# RelaySchematic.net
KiCad netlist of a schematic drawn in Altium Designer
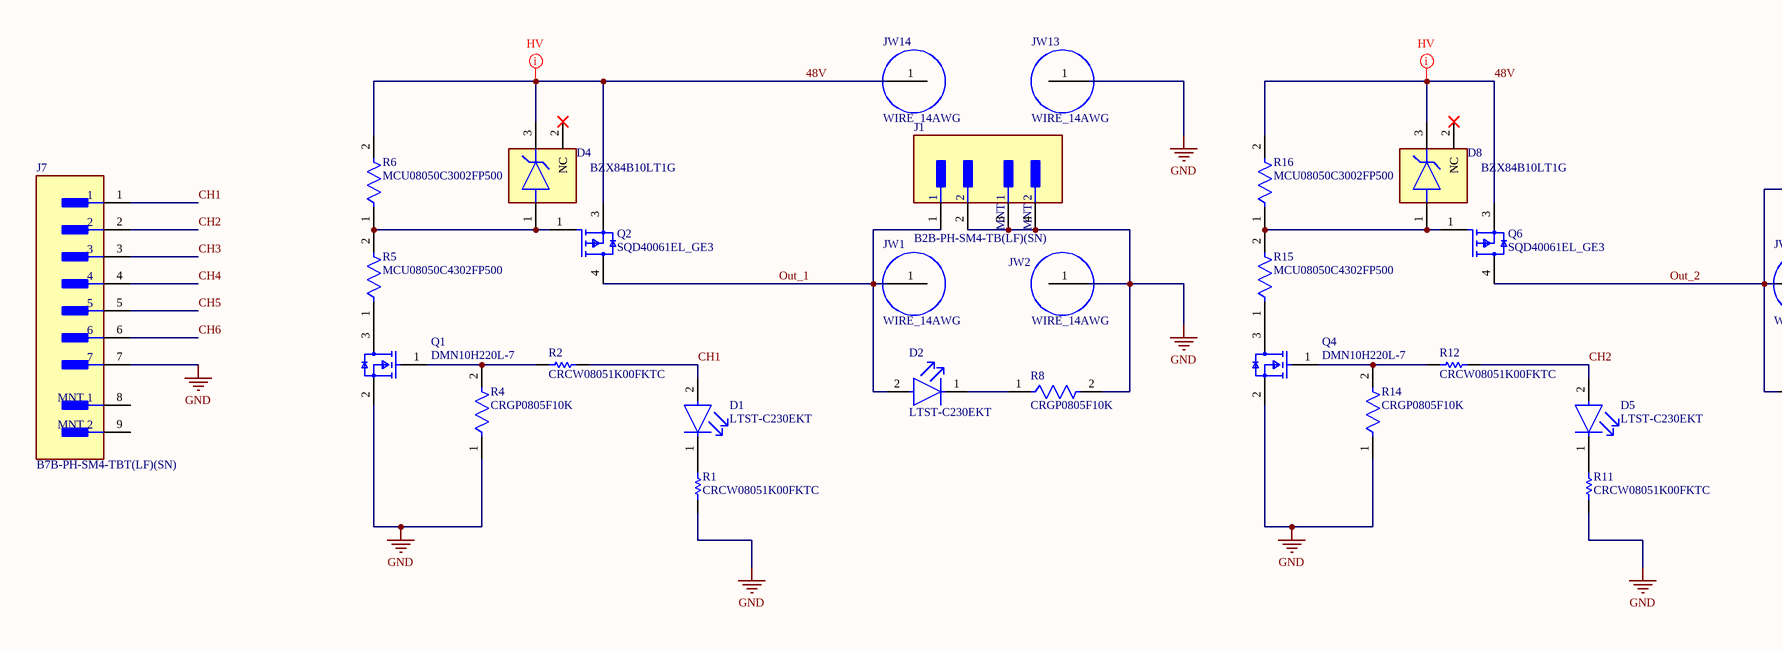
[diagram p0: RelaySchematic.SchDoc, left]
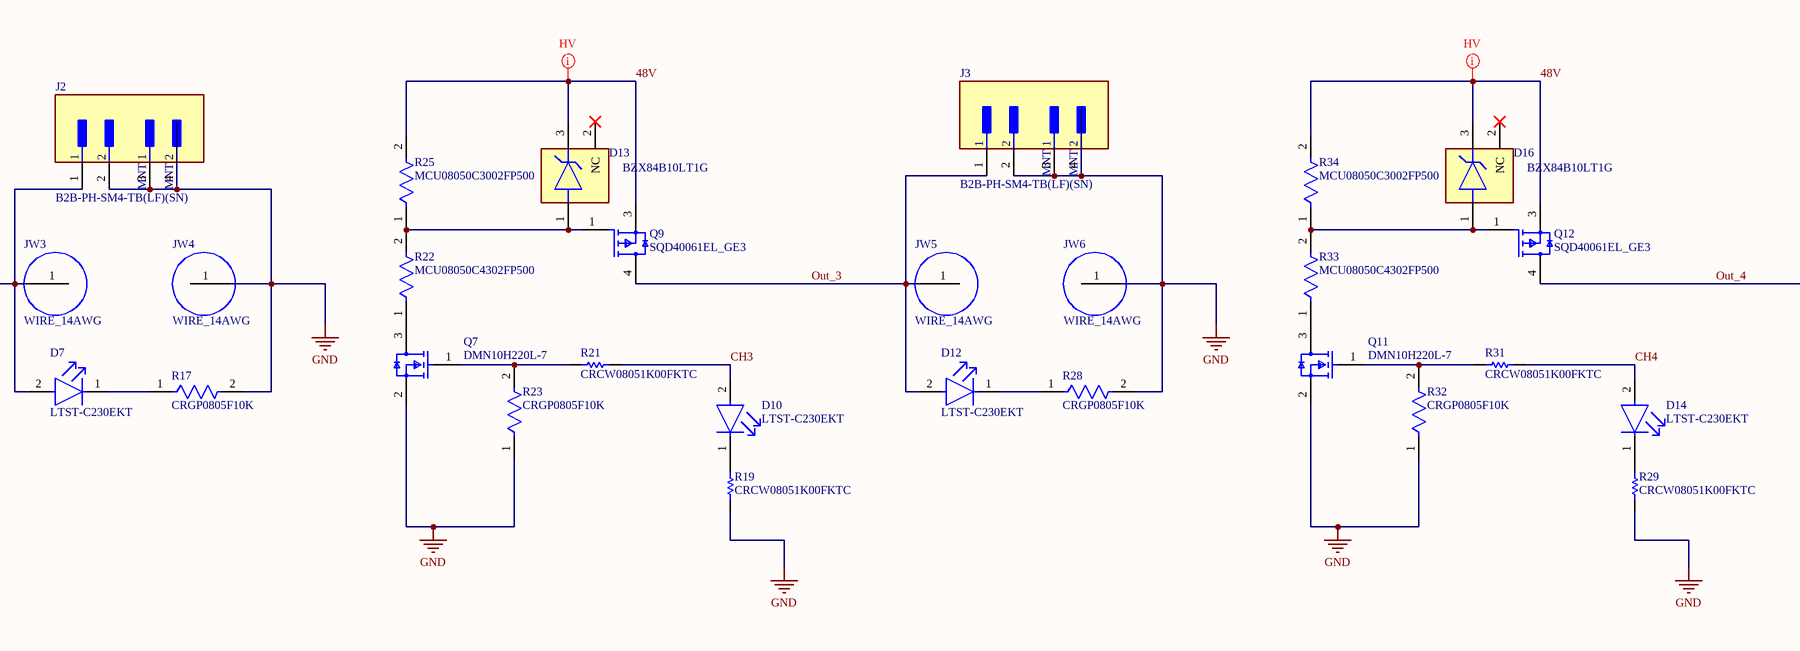
[diagram p1: RelaySchematic.SchDoc, middle]
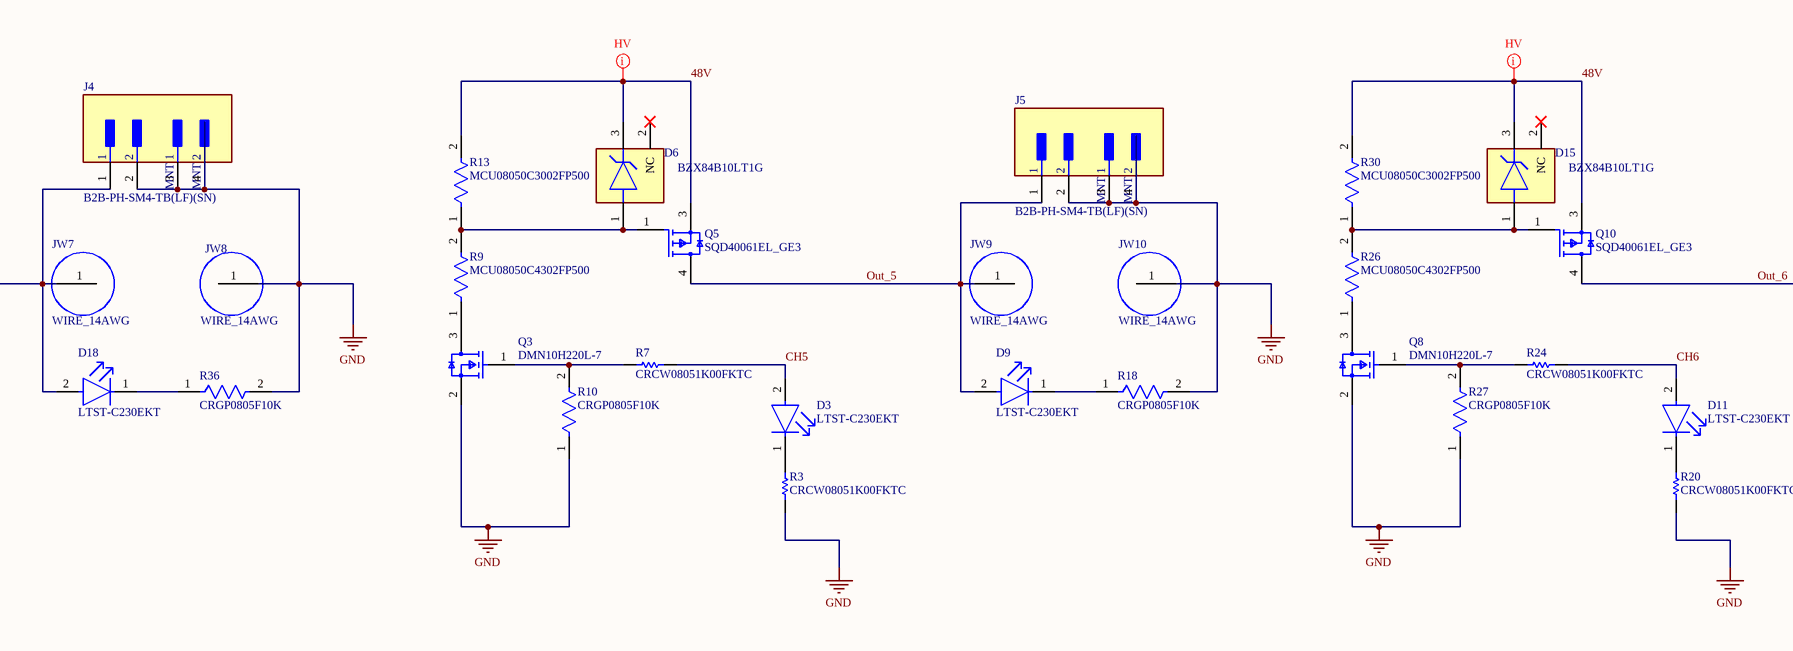
[diagram p2: RelaySchematic.SchDoc, right]

(export (version "E")
  (design (tool "Eeschema 10.0.6"))
  (components
    (comp (ref "D1")
      (value "LTST-C230EKT")
      (footprint "FP-LTST-C230EKT-MFG")
      (description "LED RED CLEAR CHIP SMD")
      (libsource (lib "Altium Content Vault") (part "8706943c75ba83719d021d2fdc84c58"))
    )
    (comp (ref "D2")
      (value "LTST-C230EKT")
      (footprint "FP-LTST-C230EKT-MFG")
      (description "LED RED CLEAR CHIP SMD")
      (libsource (lib "Altium Content Vault") (part "8706943c75ba83719d021d2fdc84c58"))
    )
    (comp (ref "D3")
      (value "LTST-C230EKT")
      (footprint "FP-LTST-C230EKT-MFG")
      (description "LED RED CLEAR CHIP SMD")
      (libsource (lib "Altium Content Vault") (part "8706943c75ba83719d021d2fdc84c58"))
    )
    (comp (ref "D4")
      (value "BZX84B10LT1G")
      (footprint "FP-318-MFG")
      (description "BZX84B10LT1G Diode Zener Single 10V 225mW 3-Pin SOT-23 T/R - Tape and Reel")
      (fields (field (name "TOLERANCE") "2%"))
      (libsource (lib "Altium Content Vault") (part "8a8a49ff936b93115747ed1a883bdcd"))
    )
    (comp (ref "D5")
      (value "LTST-C230EKT")
      (footprint "FP-LTST-C230EKT-MFG")
      (description "LED RED CLEAR CHIP SMD")
      (libsource (lib "Altium Content Vault") (part "8706943c75ba83719d021d2fdc84c58"))
    )
    (comp (ref "D6")
      (value "BZX84B10LT1G")
      (footprint "FP-318-MFG")
      (description "BZX84B10LT1G Diode Zener Single 10V 225mW 3-Pin SOT-23 T/R - Tape and Reel")
      (fields (field (name "TOLERANCE") "2%"))
      (libsource (lib "Altium Content Vault") (part "8a8a49ff936b93115747ed1a883bdcd"))
    )
    (comp (ref "D7")
      (value "LTST-C230EKT")
      (footprint "FP-LTST-C230EKT-MFG")
      (description "LED RED CLEAR CHIP SMD")
      (libsource (lib "Altium Content Vault") (part "8706943c75ba83719d021d2fdc84c58"))
    )
    (comp (ref "D8")
      (value "BZX84B10LT1G")
      (footprint "FP-318-MFG")
      (description "BZX84B10LT1G Diode Zener Single 10V 225mW 3-Pin SOT-23 T/R - Tape and Reel")
      (fields (field (name "TOLERANCE") "2%"))
      (libsource (lib "Altium Content Vault") (part "8a8a49ff936b93115747ed1a883bdcd"))
    )
    (comp (ref "D9")
      (value "LTST-C230EKT")
      (footprint "FP-LTST-C230EKT-MFG")
      (description "LED RED CLEAR CHIP SMD")
      (libsource (lib "Altium Content Vault") (part "8706943c75ba83719d021d2fdc84c58"))
    )
    (comp (ref "D10")
      (value "LTST-C230EKT")
      (footprint "FP-LTST-C230EKT-MFG")
      (description "LED RED CLEAR CHIP SMD")
      (libsource (lib "Altium Content Vault") (part "8706943c75ba83719d021d2fdc84c58"))
    )
    (comp (ref "D11")
      (value "LTST-C230EKT")
      (footprint "FP-LTST-C230EKT-MFG")
      (description "LED RED CLEAR CHIP SMD")
      (libsource (lib "Altium Content Vault") (part "8706943c75ba83719d021d2fdc84c58"))
    )
    (comp (ref "D12")
      (value "LTST-C230EKT")
      (footprint "FP-LTST-C230EKT-MFG")
      (description "LED RED CLEAR CHIP SMD")
      (libsource (lib "Altium Content Vault") (part "8706943c75ba83719d021d2fdc84c58"))
    )
    (comp (ref "D13")
      (value "BZX84B10LT1G")
      (footprint "FP-318-MFG")
      (description "BZX84B10LT1G Diode Zener Single 10V 225mW 3-Pin SOT-23 T/R - Tape and Reel")
      (fields (field (name "TOLERANCE") "2%"))
      (libsource (lib "Altium Content Vault") (part "8a8a49ff936b93115747ed1a883bdcd"))
    )
    (comp (ref "D14")
      (value "LTST-C230EKT")
      (footprint "FP-LTST-C230EKT-MFG")
      (description "LED RED CLEAR CHIP SMD")
      (libsource (lib "Altium Content Vault") (part "8706943c75ba83719d021d2fdc84c58"))
    )
    (comp (ref "D15")
      (value "BZX84B10LT1G")
      (footprint "FP-318-MFG")
      (description "BZX84B10LT1G Diode Zener Single 10V 225mW 3-Pin SOT-23 T/R - Tape and Reel")
      (fields (field (name "TOLERANCE") "2%"))
      (libsource (lib "Altium Content Vault") (part "8a8a49ff936b93115747ed1a883bdcd"))
    )
    (comp (ref "D16")
      (value "BZX84B10LT1G")
      (footprint "FP-318-MFG")
      (description "BZX84B10LT1G Diode Zener Single 10V 225mW 3-Pin SOT-23 T/R - Tape and Reel")
      (fields (field (name "TOLERANCE") "2%"))
      (libsource (lib "Altium Content Vault") (part "8a8a49ff936b93115747ed1a883bdcd"))
    )
    (comp (ref "D17")
      (value "LTST-C230EKT")
      (footprint "FP-LTST-C230EKT-MFG")
      (description "LED RED CLEAR CHIP SMD")
      (libsource (lib "Altium Content Vault") (part "8706943c75ba83719d021d2fdc84c58"))
    )
    (comp (ref "D18")
      (value "LTST-C230EKT")
      (footprint "FP-LTST-C230EKT-MFG")
      (description "LED RED CLEAR CHIP SMD")
      (libsource (lib "Altium Content Vault") (part "8706943c75ba83719d021d2fdc84c58"))
    )
    (comp (ref "J1")
      (value "B2B-PH-SM4-TB(LF)(SN)")
      (footprint "FP-B2B-PH-SM4-TB_LF_SN-MFG")
      (description "CONN HEADER SMD 2POS 2MM")
      (libsource (lib "Altium Content Vault") (part "56ec3178a87b3978bdc1b3682cd516a"))
    )
    (comp (ref "J2")
      (value "B2B-PH-SM4-TB(LF)(SN)")
      (footprint "FP-B2B-PH-SM4-TB_LF_SN-MFG")
      (description "CONN HEADER SMD 2POS 2MM")
      (libsource (lib "Altium Content Vault") (part "56ec3178a87b3978bdc1b3682cd516a"))
    )
    (comp (ref "J3")
      (value "B2B-PH-SM4-TB(LF)(SN)")
      (footprint "FP-B2B-PH-SM4-TB_LF_SN-MFG")
      (description "CONN HEADER SMD 2POS 2MM")
      (libsource (lib "Altium Content Vault") (part "56ec3178a87b3978bdc1b3682cd516a"))
    )
    (comp (ref "J4")
      (value "B2B-PH-SM4-TB(LF)(SN)")
      (footprint "FP-B2B-PH-SM4-TB_LF_SN-MFG")
      (description "CONN HEADER SMD 2POS 2MM")
      (libsource (lib "Altium Content Vault") (part "56ec3178a87b3978bdc1b3682cd516a"))
    )
    (comp (ref "J5")
      (value "B2B-PH-SM4-TB(LF)(SN)")
      (footprint "FP-B2B-PH-SM4-TB_LF_SN-MFG")
      (description "CONN HEADER SMD 2POS 2MM")
      (libsource (lib "Altium Content Vault") (part "56ec3178a87b3978bdc1b3682cd516a"))
    )
    (comp (ref "J6")
      (value "B2B-PH-SM4-TB(LF)(SN)")
      (footprint "FP-B2B-PH-SM4-TB_LF_SN-MFG")
      (description "CONN HEADER SMD 2POS 2MM")
      (libsource (lib "Altium Content Vault") (part "56ec3178a87b3978bdc1b3682cd516a"))
    )
    (comp (ref "J7")
      (value "B7B-PH-SM4-TBT(LF)(SN)")
      (footprint "FP-B7B-PH-SM4-TBT_LF_SN-MFG")
      (description "CONN HEADER SMD 7POS 2MM")
      (libsource (lib "Altium Content Vault") (part "b0abd15a4b949e48c0a2e6945bb7dcd"))
    )
    (comp (ref "JW1")
      (value "WIRE_14AWG")
      (footprint "WIRE_14AWG_PTH")
      (libsource (lib "14AWGSch") (part "WIRE_14AWG"))
    )
    (comp (ref "JW2")
      (value "WIRE_14AWG")
      (footprint "WIRE_14AWG_PTH")
      (libsource (lib "14AWGSch") (part "WIRE_14AWG"))
    )
    (comp (ref "JW3")
      (value "WIRE_14AWG")
      (footprint "WIRE_14AWG_PTH")
      (libsource (lib "14AWGSch") (part "WIRE_14AWG"))
    )
    (comp (ref "JW4")
      (value "WIRE_14AWG")
      (footprint "WIRE_14AWG_PTH")
      (libsource (lib "14AWGSch") (part "WIRE_14AWG"))
    )
    (comp (ref "JW5")
      (value "WIRE_14AWG")
      (footprint "WIRE_14AWG_PTH")
      (libsource (lib "14AWGSch") (part "WIRE_14AWG"))
    )
    (comp (ref "JW6")
      (value "WIRE_14AWG")
      (footprint "WIRE_14AWG_PTH")
      (libsource (lib "14AWGSch") (part "WIRE_14AWG"))
    )
    (comp (ref "JW7")
      (value "WIRE_14AWG")
      (footprint "WIRE_14AWG_PTH")
      (libsource (lib "14AWGSch") (part "WIRE_14AWG"))
    )
    (comp (ref "JW8")
      (value "WIRE_14AWG")
      (footprint "WIRE_14AWG_PTH")
      (libsource (lib "14AWGSch") (part "WIRE_14AWG"))
    )
    (comp (ref "JW9")
      (value "WIRE_14AWG")
      (footprint "WIRE_14AWG_PTH")
      (libsource (lib "14AWGSch") (part "WIRE_14AWG"))
    )
    (comp (ref "JW10")
      (value "WIRE_14AWG")
      (footprint "WIRE_14AWG_PTH")
      (libsource (lib "14AWGSch") (part "WIRE_14AWG"))
    )
    (comp (ref "JW11")
      (value "WIRE_14AWG")
      (footprint "WIRE_14AWG_PTH")
      (libsource (lib "14AWGSch") (part "WIRE_14AWG"))
    )
    (comp (ref "JW12")
      (value "WIRE_14AWG")
      (footprint "WIRE_14AWG_PTH")
      (libsource (lib "14AWGSch") (part "WIRE_14AWG"))
    )
    (comp (ref "JW13")
      (value "WIRE_14AWG")
      (footprint "WIRE_14AWG_PTH")
      (libsource (lib "14AWGSch") (part "WIRE_14AWG"))
    )
    (comp (ref "JW14")
      (value "WIRE_14AWG")
      (footprint "WIRE_14AWG_PTH")
      (libsource (lib "14AWGSch") (part "WIRE_14AWG"))
    )
    (comp (ref "Q1")
      (value "DMN10H220L-7")
      (footprint "FP-SOT23-MFG")
      (description "MOSFET N-CH 100V 1.6A SOT-23")
      (fields
        (field (name "MANUFACTURER") "Diodes Inc.")
        (field (name "OCTOPART") "https://octopart.com/dmn10h220l-7-diodes+inc.-38898610")
      )
      (libsource (lib "Altium Content Vault") (part "3b9c635fedb024a5347a57b145af9cc"))
    )
    (comp (ref "Q2")
      (value "SQD40061EL_GE3")
      (footprint "FP-T13-0592-MFG")
      (description "MOSFET P-CH 40V 100A TO252AA")
      (libsource (lib "Altium Content Vault") (part "96541cbfd339c2285289298bddcc93e"))
    )
    (comp (ref "Q3")
      (value "DMN10H220L-7")
      (footprint "FP-SOT23-MFG")
      (description "MOSFET N-CH 100V 1.6A SOT-23")
      (fields
        (field (name "MANUFACTURER") "Diodes Inc.")
        (field (name "OCTOPART") "https://octopart.com/dmn10h220l-7-diodes+inc.-38898610")
      )
      (libsource (lib "Altium Content Vault") (part "3b9c635fedb024a5347a57b145af9cc"))
    )
    (comp (ref "Q4")
      (value "DMN10H220L-7")
      (footprint "FP-SOT23-MFG")
      (description "MOSFET N-CH 100V 1.6A SOT-23")
      (fields
        (field (name "MANUFACTURER") "Diodes Inc.")
        (field (name "OCTOPART") "https://octopart.com/dmn10h220l-7-diodes+inc.-38898610")
      )
      (libsource (lib "Altium Content Vault") (part "3b9c635fedb024a5347a57b145af9cc"))
    )
    (comp (ref "Q5")
      (value "SQD40061EL_GE3")
      (footprint "FP-T13-0592-MFG")
      (description "MOSFET P-CH 40V 100A TO252AA")
      (libsource (lib "Altium Content Vault") (part "96541cbfd339c2285289298bddcc93e"))
    )
    (comp (ref "Q6")
      (value "SQD40061EL_GE3")
      (footprint "FP-T13-0592-MFG")
      (description "MOSFET P-CH 40V 100A TO252AA")
      (libsource (lib "Altium Content Vault") (part "96541cbfd339c2285289298bddcc93e"))
    )
    (comp (ref "Q7")
      (value "DMN10H220L-7")
      (footprint "FP-SOT23-MFG")
      (description "MOSFET N-CH 100V 1.6A SOT-23")
      (fields
        (field (name "MANUFACTURER") "Diodes Inc.")
        (field (name "OCTOPART") "https://octopart.com/dmn10h220l-7-diodes+inc.-38898610")
      )
      (libsource (lib "Altium Content Vault") (part "3b9c635fedb024a5347a57b145af9cc"))
    )
    (comp (ref "Q8")
      (value "DMN10H220L-7")
      (footprint "FP-SOT23-MFG")
      (description "MOSFET N-CH 100V 1.6A SOT-23")
      (fields
        (field (name "MANUFACTURER") "Diodes Inc.")
        (field (name "OCTOPART") "https://octopart.com/dmn10h220l-7-diodes+inc.-38898610")
      )
      (libsource (lib "Altium Content Vault") (part "3b9c635fedb024a5347a57b145af9cc"))
    )
    (comp (ref "Q9")
      (value "SQD40061EL_GE3")
      (footprint "FP-T13-0592-MFG")
      (description "MOSFET P-CH 40V 100A TO252AA")
      (libsource (lib "Altium Content Vault") (part "96541cbfd339c2285289298bddcc93e"))
    )
    (comp (ref "Q10")
      (value "SQD40061EL_GE3")
      (footprint "FP-T13-0592-MFG")
      (description "MOSFET P-CH 40V 100A TO252AA")
      (libsource (lib "Altium Content Vault") (part "96541cbfd339c2285289298bddcc93e"))
    )
    (comp (ref "Q11")
      (value "DMN10H220L-7")
      (footprint "FP-SOT23-MFG")
      (description "MOSFET N-CH 100V 1.6A SOT-23")
      (fields
        (field (name "MANUFACTURER") "Diodes Inc.")
        (field (name "OCTOPART") "https://octopart.com/dmn10h220l-7-diodes+inc.-38898610")
      )
      (libsource (lib "Altium Content Vault") (part "3b9c635fedb024a5347a57b145af9cc"))
    )
    (comp (ref "Q12")
      (value "SQD40061EL_GE3")
      (footprint "FP-T13-0592-MFG")
      (description "MOSFET P-CH 40V 100A TO252AA")
      (libsource (lib "Altium Content Vault") (part "96541cbfd339c2285289298bddcc93e"))
    )
    (comp (ref "R1")
      (value "CRCW08051K00FKTC")
      (footprint "RESC2013X50X30ML20T20")
      (fields (field (name "MANUFACTURER") "Vishay Dale"))
      (libsource (lib "Altium Content Vault") (part "RES"))
    )
    (comp (ref "R2")
      (value "CRCW08051K00FKTC")
      (footprint "RESC2013X50X30ML20T20")
      (fields (field (name "MANUFACTURER") "Vishay Dale"))
      (libsource (lib "Altium Content Vault") (part "RES"))
    )
    (comp (ref "R3")
      (value "CRCW08051K00FKTC")
      (footprint "RESC2013X50X30ML20T20")
      (fields (field (name "MANUFACTURER") "Vishay Dale"))
      (libsource (lib "Altium Content Vault") (part "RES"))
    )
    (comp (ref "R4")
      (value "CRGP0805F10K")
      (footprint "FP-CRGP0805-IPC_C")
      (description "CRGP0805 10KΩ 0.33W ±100ppm/°C 1% 150V")
      (fields (field (name "MANUFACTURER") "TE"))
      (libsource (lib "Altium Content Vault") (part "1029c3af85768c4190bb7ad29bc67b5"))
    )
    (comp (ref "R5")
      (value "MCU08050C4302FP500")
      (footprint "FP-MCU0805-IPC_C")
      (description "RES 1.05K OHM 0.5% 1/5W 0805")
      (fields (field (name "TOLERANCE") "1%"))
      (libsource (lib "Altium Content Vault") (part "1029c3af85768c4190bb7ad29bc67b5"))
    )
    (comp (ref "R6")
      (value "MCU08050C3002FP500")
      (footprint "FP-MCU0805-MFG")
      (description "RES 1.05K OHM 0.5% 1/5W 0805")
      (fields (field (name "TOLERANCE") "1%"))
      (libsource (lib "Altium Content Vault") (part "1029c3af85768c4190bb7ad29bc67b5"))
    )
    (comp (ref "R7")
      (value "CRCW08051K00FKTC")
      (footprint "RESC2013X50X30ML20T20")
      (fields (field (name "MANUFACTURER") "Vishay Dale"))
      (libsource (lib "Altium Content Vault") (part "RES"))
    )
    (comp (ref "R8")
      (value "CRGP0805F10K")
      (footprint "FP-CRGP0805-IPC_C")
      (description "CRGP0805 10KΩ 0.33W ±100ppm/°C 1% 150V")
      (fields (field (name "MANUFACTURER") "TE"))
      (libsource (lib "Altium Content Vault") (part "1029c3af85768c4190bb7ad29bc67b5"))
    )
    (comp (ref "R9")
      (value "MCU08050C4302FP500")
      (footprint "FP-MCU0805-IPC_C")
      (description "RES 1.05K OHM 0.5% 1/5W 0805")
      (fields (field (name "TOLERANCE") "1%"))
      (libsource (lib "Altium Content Vault") (part "1029c3af85768c4190bb7ad29bc67b5"))
    )
    (comp (ref "R10")
      (value "CRGP0805F10K")
      (footprint "FP-CRGP0805-IPC_C")
      (description "CRGP0805 10KΩ 0.33W ±100ppm/°C 1% 150V")
      (fields (field (name "MANUFACTURER") "TE"))
      (libsource (lib "Altium Content Vault") (part "1029c3af85768c4190bb7ad29bc67b5"))
    )
    (comp (ref "R11")
      (value "CRCW08051K00FKTC")
      (footprint "RESC2013X50X30ML20T20")
      (fields (field (name "MANUFACTURER") "Vishay Dale"))
      (libsource (lib "Altium Content Vault") (part "RES"))
    )
    (comp (ref "R12")
      (value "CRCW08051K00FKTC")
      (footprint "RESC2013X50X30ML20T20")
      (fields (field (name "MANUFACTURER") "Vishay Dale"))
      (libsource (lib "Altium Content Vault") (part "RES"))
    )
    (comp (ref "R13")
      (value "MCU08050C3002FP500")
      (footprint "FP-MCU0805-MFG")
      (description "RES 1.05K OHM 0.5% 1/5W 0805")
      (fields (field (name "TOLERANCE") "1%"))
      (libsource (lib "Altium Content Vault") (part "1029c3af85768c4190bb7ad29bc67b5"))
    )
    (comp (ref "R14")
      (value "CRGP0805F10K")
      (footprint "FP-CRGP0805-IPC_C")
      (description "CRGP0805 10KΩ 0.33W ±100ppm/°C 1% 150V")
      (fields (field (name "MANUFACTURER") "TE"))
      (libsource (lib "Altium Content Vault") (part "1029c3af85768c4190bb7ad29bc67b5"))
    )
    (comp (ref "R15")
      (value "MCU08050C4302FP500")
      (footprint "FP-MCU0805-IPC_C")
      (description "RES 1.05K OHM 0.5% 1/5W 0805")
      (fields (field (name "TOLERANCE") "1%"))
      (libsource (lib "Altium Content Vault") (part "1029c3af85768c4190bb7ad29bc67b5"))
    )
    (comp (ref "R16")
      (value "MCU08050C3002FP500")
      (footprint "FP-MCU0805-MFG")
      (description "RES 1.05K OHM 0.5% 1/5W 0805")
      (fields (field (name "TOLERANCE") "1%"))
      (libsource (lib "Altium Content Vault") (part "1029c3af85768c4190bb7ad29bc67b5"))
    )
    (comp (ref "R17")
      (value "CRGP0805F10K")
      (footprint "FP-CRGP0805-IPC_C")
      (description "CRGP0805 10KΩ 0.33W ±100ppm/°C 1% 150V")
      (fields (field (name "MANUFACTURER") "TE"))
      (libsource (lib "Altium Content Vault") (part "1029c3af85768c4190bb7ad29bc67b5"))
    )
    (comp (ref "R18")
      (value "CRGP0805F10K")
      (footprint "FP-CRGP0805-IPC_C")
      (description "CRGP0805 10KΩ 0.33W ±100ppm/°C 1% 150V")
      (fields (field (name "MANUFACTURER") "TE"))
      (libsource (lib "Altium Content Vault") (part "1029c3af85768c4190bb7ad29bc67b5"))
    )
    (comp (ref "R19")
      (value "CRCW08051K00FKTC")
      (footprint "RESC2013X50X30ML20T20")
      (fields (field (name "MANUFACTURER") "Vishay Dale"))
      (libsource (lib "Altium Content Vault") (part "RES"))
    )
    (comp (ref "R20")
      (value "CRCW08051K00FKTC")
      (footprint "RESC2013X50X30ML20T20")
      (fields (field (name "MANUFACTURER") "Vishay Dale"))
      (libsource (lib "Altium Content Vault") (part "RES"))
    )
    (comp (ref "R21")
      (value "CRCW08051K00FKTC")
      (footprint "RESC2013X50X30ML20T20")
      (fields (field (name "MANUFACTURER") "Vishay Dale"))
      (libsource (lib "Altium Content Vault") (part "RES"))
    )
    (comp (ref "R22")
      (value "MCU08050C4302FP500")
      (footprint "FP-MCU0805-IPC_C")
      (description "RES 1.05K OHM 0.5% 1/5W 0805")
      (fields (field (name "TOLERANCE") "1%"))
      (libsource (lib "Altium Content Vault") (part "1029c3af85768c4190bb7ad29bc67b5"))
    )
    (comp (ref "R23")
      (value "CRGP0805F10K")
      (footprint "FP-CRGP0805-IPC_C")
      (description "CRGP0805 10KΩ 0.33W ±100ppm/°C 1% 150V")
      (fields (field (name "MANUFACTURER") "TE"))
      (libsource (lib "Altium Content Vault") (part "1029c3af85768c4190bb7ad29bc67b5"))
    )
    (comp (ref "R24")
      (value "CRCW08051K00FKTC")
      (footprint "RESC2013X50X30ML20T20")
      (fields (field (name "MANUFACTURER") "Vishay Dale"))
      (libsource (lib "Altium Content Vault") (part "RES"))
    )
    (comp (ref "R25")
      (value "MCU08050C3002FP500")
      (footprint "FP-MCU0805-MFG")
      (description "RES 1.05K OHM 0.5% 1/5W 0805")
      (fields (field (name "TOLERANCE") "1%"))
      (libsource (lib "Altium Content Vault") (part "1029c3af85768c4190bb7ad29bc67b5"))
    )
    (comp (ref "R26")
      (value "MCU08050C4302FP500")
      (footprint "FP-MCU0805-IPC_C")
      (description "RES 1.05K OHM 0.5% 1/5W 0805")
      (fields (field (name "TOLERANCE") "1%"))
      (libsource (lib "Altium Content Vault") (part "1029c3af85768c4190bb7ad29bc67b5"))
    )
    (comp (ref "R27")
      (value "CRGP0805F10K")
      (footprint "FP-CRGP0805-IPC_C")
      (description "CRGP0805 10KΩ 0.33W ±100ppm/°C 1% 150V")
      (fields (field (name "MANUFACTURER") "TE"))
      (libsource (lib "Altium Content Vault") (part "1029c3af85768c4190bb7ad29bc67b5"))
    )
    (comp (ref "R28")
      (value "CRGP0805F10K")
      (footprint "FP-CRGP0805-IPC_C")
      (description "CRGP0805 10KΩ 0.33W ±100ppm/°C 1% 150V")
      (fields (field (name "MANUFACTURER") "TE"))
      (libsource (lib "Altium Content Vault") (part "1029c3af85768c4190bb7ad29bc67b5"))
    )
    (comp (ref "R29")
      (value "CRCW08051K00FKTC")
      (footprint "RESC2013X50X30ML20T20")
      (fields (field (name "MANUFACTURER") "Vishay Dale"))
      (libsource (lib "Altium Content Vault") (part "RES"))
    )
    (comp (ref "R30")
      (value "MCU08050C3002FP500")
      (footprint "FP-MCU0805-MFG")
      (description "RES 1.05K OHM 0.5% 1/5W 0805")
      (fields (field (name "TOLERANCE") "1%"))
      (libsource (lib "Altium Content Vault") (part "1029c3af85768c4190bb7ad29bc67b5"))
    )
    (comp (ref "R31")
      (value "CRCW08051K00FKTC")
      (footprint "RESC2013X50X30ML20T20")
      (fields (field (name "MANUFACTURER") "Vishay Dale"))
      (libsource (lib "Altium Content Vault") (part "RES"))
    )
    (comp (ref "R32")
      (value "CRGP0805F10K")
      (footprint "FP-CRGP0805-IPC_C")
      (description "CRGP0805 10KΩ 0.33W ±100ppm/°C 1% 150V")
      (fields (field (name "MANUFACTURER") "TE"))
      (libsource (lib "Altium Content Vault") (part "1029c3af85768c4190bb7ad29bc67b5"))
    )
    (comp (ref "R33")
      (value "MCU08050C4302FP500")
      (footprint "FP-MCU0805-IPC_C")
      (description "RES 1.05K OHM 0.5% 1/5W 0805")
      (fields (field (name "TOLERANCE") "1%"))
      (libsource (lib "Altium Content Vault") (part "1029c3af85768c4190bb7ad29bc67b5"))
    )
    (comp (ref "R34")
      (value "MCU08050C3002FP500")
      (footprint "FP-MCU0805-MFG")
      (description "RES 1.05K OHM 0.5% 1/5W 0805")
      (fields (field (name "TOLERANCE") "1%"))
      (libsource (lib "Altium Content Vault") (part "1029c3af85768c4190bb7ad29bc67b5"))
    )
    (comp (ref "R35")
      (value "CRGP0805F10K")
      (footprint "FP-CRGP0805-IPC_C")
      (description "CRGP0805 10KΩ 0.33W ±100ppm/°C 1% 150V")
      (fields (field (name "MANUFACTURER") "TE"))
      (libsource (lib "Altium Content Vault") (part "1029c3af85768c4190bb7ad29bc67b5"))
    )
    (comp (ref "R36")
      (value "CRGP0805F10K")
      (footprint "FP-CRGP0805-IPC_C")
      (description "CRGP0805 10KΩ 0.33W ±100ppm/°C 1% 150V")
      (fields (field (name "MANUFACTURER") "TE"))
      (libsource (lib "Altium Content Vault") (part "1029c3af85768c4190bb7ad29bc67b5"))
    )
  )
  (nets
    (net (code "1") (name "/48V") (class "Default")
      (node (ref "D13") (pin "3") (pinfunction "C_3") (pintype "passive"))
      (node (ref "D15") (pin "3") (pinfunction "C_3") (pintype "passive"))
      (node (ref "D16") (pin "3") (pinfunction "C_3") (pintype "passive"))
      (node (ref "D4") (pin "3") (pinfunction "C_3") (pintype "passive"))
      (node (ref "D6") (pin "3") (pinfunction "C_3") (pintype "passive"))
      (node (ref "D8") (pin "3") (pinfunction "C_3") (pintype "passive"))
      (node (ref "JW14") (pin "1") (pinfunction "0_1") (pintype "passive"))
      (node (ref "Q10") (pin "3") (pinfunction "S_3") (pintype "passive"))
      (node (ref "Q12") (pin "3") (pinfunction "S_3") (pintype "passive"))
      (node (ref "Q2") (pin "3") (pinfunction "S_3") (pintype "passive"))
      (node (ref "Q5") (pin "3") (pinfunction "S_3") (pintype "passive"))
      (node (ref "Q6") (pin "3") (pinfunction "S_3") (pintype "passive"))
      (node (ref "Q9") (pin "3") (pinfunction "S_3") (pintype "passive"))
      (node (ref "R13") (pin "2") (pinfunction "2_2") (pintype "passive"))
      (node (ref "R16") (pin "2") (pinfunction "2_2") (pintype "passive"))
      (node (ref "R25") (pin "2") (pinfunction "2_2") (pintype "passive"))
      (node (ref "R30") (pin "2") (pinfunction "2_2") (pintype "passive"))
      (node (ref "R34") (pin "2") (pinfunction "2_2") (pintype "passive"))
      (node (ref "R6") (pin "2") (pinfunction "2_2") (pintype "passive"))
    )
    (net (code "2") (name "/CH1") (class "Default")
      (node (ref "D1") (pin "2") (pinfunction "A_2") (pintype "passive"))
      (node (ref "J7") (pin "1") (pinfunction "1_1") (pintype "passive"))
      (node (ref "R2") (pin "2") (pinfunction "2_2") (pintype "passive"))
    )
    (net (code "3") (name "/CH2") (class "Default")
      (node (ref "D5") (pin "2") (pinfunction "A_2") (pintype "passive"))
      (node (ref "J7") (pin "2") (pinfunction "2_2") (pintype "passive"))
      (node (ref "R12") (pin "2") (pinfunction "2_2") (pintype "passive"))
    )
    (net (code "4") (name "/CH3") (class "Default")
      (node (ref "D10") (pin "2") (pinfunction "A_2") (pintype "passive"))
      (node (ref "J7") (pin "3") (pinfunction "3_3") (pintype "passive"))
      (node (ref "R21") (pin "2") (pinfunction "2_2") (pintype "passive"))
    )
    (net (code "5") (name "/CH4") (class "Default")
      (node (ref "D14") (pin "2") (pinfunction "A_2") (pintype "passive"))
      (node (ref "J7") (pin "4") (pinfunction "4_4") (pintype "passive"))
      (node (ref "R31") (pin "2") (pinfunction "2_2") (pintype "passive"))
    )
    (net (code "6") (name "/CH5") (class "Default")
      (node (ref "D3") (pin "2") (pinfunction "A_2") (pintype "passive"))
      (node (ref "J7") (pin "5") (pinfunction "5_5") (pintype "passive"))
      (node (ref "R7") (pin "2") (pinfunction "2_2") (pintype "passive"))
    )
    (net (code "7") (name "/CH6") (class "Default")
      (node (ref "D11") (pin "2") (pinfunction "A_2") (pintype "passive"))
      (node (ref "J7") (pin "6") (pinfunction "6_6") (pintype "passive"))
      (node (ref "R24") (pin "2") (pinfunction "2_2") (pintype "passive"))
    )
    (net (code "8") (name "/Out_1") (class "Default")
      (node (ref "D2") (pin "2") (pinfunction "A_2") (pintype "passive"))
      (node (ref "J1") (pin "1") (pinfunction "1_1") (pintype "passive"))
      (node (ref "JW1") (pin "1") (pinfunction "0_1") (pintype "passive"))
      (node (ref "Q2") (pin "4") (pinfunction "D_4") (pintype "passive"))
    )
    (net (code "9") (name "/Out_2") (class "Default")
      (node (ref "D7") (pin "2") (pinfunction "A_2") (pintype "passive"))
      (node (ref "J2") (pin "1") (pinfunction "1_1") (pintype "passive"))
      (node (ref "JW3") (pin "1") (pinfunction "0_1") (pintype "passive"))
      (node (ref "Q6") (pin "4") (pinfunction "D_4") (pintype "passive"))
    )
    (net (code "10") (name "/Out_3") (class "Default")
      (node (ref "D12") (pin "2") (pinfunction "A_2") (pintype "passive"))
      (node (ref "J3") (pin "1") (pinfunction "1_1") (pintype "passive"))
      (node (ref "JW5") (pin "1") (pinfunction "0_1") (pintype "passive"))
      (node (ref "Q9") (pin "4") (pinfunction "D_4") (pintype "passive"))
    )
    (net (code "11") (name "/Out_4") (class "Default")
      (node (ref "D18") (pin "2") (pinfunction "A_2") (pintype "passive"))
      (node (ref "J4") (pin "1") (pinfunction "1_1") (pintype "passive"))
      (node (ref "JW7") (pin "1") (pinfunction "0_1") (pintype "passive"))
      (node (ref "Q12") (pin "4") (pinfunction "D_4") (pintype "passive"))
    )
    (net (code "12") (name "/Out_5") (class "Default")
      (node (ref "D9") (pin "2") (pinfunction "A_2") (pintype "passive"))
      (node (ref "J5") (pin "1") (pinfunction "1_1") (pintype "passive"))
      (node (ref "JW9") (pin "1") (pinfunction "0_1") (pintype "passive"))
      (node (ref "Q5") (pin "4") (pinfunction "D_4") (pintype "passive"))
    )
    (net (code "13") (name "/Out_6") (class "Default")
      (node (ref "D17") (pin "2") (pinfunction "A_2") (pintype "passive"))
      (node (ref "J6") (pin "1") (pinfunction "1_1") (pintype "passive"))
      (node (ref "JW11") (pin "1") (pinfunction "0_1") (pintype "passive"))
      (node (ref "Q10") (pin "4") (pinfunction "D_4") (pintype "passive"))
    )
    (net (code "14") (name "GND") (class "Default")
      (node (ref "J1") (pin "2") (pinfunction "2_2") (pintype "passive"))
      (node (ref "J1") (pin "3") (pinfunction "MNT_1_3") (pintype "passive"))
      (node (ref "J1") (pin "4") (pinfunction "MNT_2_4") (pintype "passive"))
      (node (ref "J2") (pin "2") (pinfunction "2_2") (pintype "passive"))
      (node (ref "J2") (pin "3") (pinfunction "MNT_1_3") (pintype "passive"))
      (node (ref "J2") (pin "4") (pinfunction "MNT_2_4") (pintype "passive"))
      (node (ref "J3") (pin "2") (pinfunction "2_2") (pintype "passive"))
      (node (ref "J3") (pin "3") (pinfunction "MNT_1_3") (pintype "passive"))
      (node (ref "J3") (pin "4") (pinfunction "MNT_2_4") (pintype "passive"))
      (node (ref "J4") (pin "2") (pinfunction "2_2") (pintype "passive"))
      (node (ref "J4") (pin "3") (pinfunction "MNT_1_3") (pintype "passive"))
      (node (ref "J4") (pin "4") (pinfunction "MNT_2_4") (pintype "passive"))
      (node (ref "J5") (pin "2") (pinfunction "2_2") (pintype "passive"))
      (node (ref "J5") (pin "3") (pinfunction "MNT_1_3") (pintype "passive"))
      (node (ref "J5") (pin "4") (pinfunction "MNT_2_4") (pintype "passive"))
      (node (ref "J6") (pin "2") (pinfunction "2_2") (pintype "passive"))
      (node (ref "J6") (pin "3") (pinfunction "MNT_1_3") (pintype "passive"))
      (node (ref "J6") (pin "4") (pinfunction "MNT_2_4") (pintype "passive"))
      (node (ref "J7") (pin "7") (pinfunction "7_7") (pintype "passive"))
      (node (ref "JW10") (pin "1") (pinfunction "0_1") (pintype "passive"))
      (node (ref "JW12") (pin "1") (pinfunction "0_1") (pintype "passive"))
      (node (ref "JW13") (pin "1") (pinfunction "0_1") (pintype "passive"))
      (node (ref "JW2") (pin "1") (pinfunction "0_1") (pintype "passive"))
      (node (ref "JW4") (pin "1") (pinfunction "0_1") (pintype "passive"))
      (node (ref "JW6") (pin "1") (pinfunction "0_1") (pintype "passive"))
      (node (ref "JW8") (pin "1") (pinfunction "0_1") (pintype "passive"))
      (node (ref "Q1") (pin "2") (pinfunction "S_2") (pintype "passive"))
      (node (ref "Q11") (pin "2") (pinfunction "S_2") (pintype "passive"))
      (node (ref "Q3") (pin "2") (pinfunction "S_2") (pintype "passive"))
      (node (ref "Q4") (pin "2") (pinfunction "S_2") (pintype "passive"))
      (node (ref "Q7") (pin "2") (pinfunction "S_2") (pintype "passive"))
      (node (ref "Q8") (pin "2") (pinfunction "S_2") (pintype "passive"))
      (node (ref "R1") (pin "1") (pinfunction "1_1") (pintype "passive"))
      (node (ref "R10") (pin "1") (pinfunction "1_1") (pintype "passive"))
      (node (ref "R11") (pin "1") (pinfunction "1_1") (pintype "passive"))
      (node (ref "R14") (pin "1") (pinfunction "1_1") (pintype "passive"))
      (node (ref "R17") (pin "2") (pinfunction "2_2") (pintype "passive"))
      (node (ref "R18") (pin "2") (pinfunction "2_2") (pintype "passive"))
      (node (ref "R19") (pin "1") (pinfunction "1_1") (pintype "passive"))
      (node (ref "R20") (pin "1") (pinfunction "1_1") (pintype "passive"))
      (node (ref "R23") (pin "1") (pinfunction "1_1") (pintype "passive"))
      (node (ref "R27") (pin "1") (pinfunction "1_1") (pintype "passive"))
      (node (ref "R28") (pin "2") (pinfunction "2_2") (pintype "passive"))
      (node (ref "R29") (pin "1") (pinfunction "1_1") (pintype "passive"))
      (node (ref "R3") (pin "1") (pinfunction "1_1") (pintype "passive"))
      (node (ref "R32") (pin "1") (pinfunction "1_1") (pintype "passive"))
      (node (ref "R35") (pin "2") (pinfunction "2_2") (pintype "passive"))
      (node (ref "R36") (pin "2") (pinfunction "2_2") (pintype "passive"))
      (node (ref "R4") (pin "1") (pinfunction "1_1") (pintype "passive"))
      (node (ref "R8") (pin "2") (pinfunction "2_2") (pintype "passive"))
    )
    (net (code "15") (name "Net-(D1-C)") (class "Default")
      (node (ref "D1") (pin "1") (pinfunction "C_1") (pintype "passive"))
      (node (ref "R1") (pin "2") (pinfunction "2_2") (pintype "passive"))
    )
    (net (code "16") (name "Net-(D2-C)") (class "Default")
      (node (ref "D2") (pin "1") (pinfunction "C_1") (pintype "passive"))
      (node (ref "R8") (pin "1") (pinfunction "1_1") (pintype "passive"))
    )
    (net (code "17") (name "Net-(D3-C)") (class "Default")
      (node (ref "D3") (pin "1") (pinfunction "C_1") (pintype "passive"))
      (node (ref "R3") (pin "2") (pinfunction "2_2") (pintype "passive"))
    )
    (net (code "18") (name "Net-(D4-A)") (class "Default")
      (node (ref "D4") (pin "1") (pinfunction "A_1") (pintype "passive"))
      (node (ref "Q2") (pin "1") (pinfunction "G_1") (pintype "passive"))
      (node (ref "R5") (pin "2") (pinfunction "2_2") (pintype "passive"))
      (node (ref "R6") (pin "1") (pinfunction "1_1") (pintype "passive"))
    )
    (net (code "19") (name "Net-(D5-C)") (class "Default")
      (node (ref "D5") (pin "1") (pinfunction "C_1") (pintype "passive"))
      (node (ref "R11") (pin "2") (pinfunction "2_2") (pintype "passive"))
    )
    (net (code "20") (name "Net-(D6-A)") (class "Default")
      (node (ref "D6") (pin "1") (pinfunction "A_1") (pintype "passive"))
      (node (ref "Q5") (pin "1") (pinfunction "G_1") (pintype "passive"))
      (node (ref "R13") (pin "1") (pinfunction "1_1") (pintype "passive"))
      (node (ref "R9") (pin "2") (pinfunction "2_2") (pintype "passive"))
    )
    (net (code "21") (name "Net-(D7-C)") (class "Default")
      (node (ref "D7") (pin "1") (pinfunction "C_1") (pintype "passive"))
      (node (ref "R17") (pin "1") (pinfunction "1_1") (pintype "passive"))
    )
    (net (code "22") (name "Net-(D8-A)") (class "Default")
      (node (ref "D8") (pin "1") (pinfunction "A_1") (pintype "passive"))
      (node (ref "Q6") (pin "1") (pinfunction "G_1") (pintype "passive"))
      (node (ref "R15") (pin "2") (pinfunction "2_2") (pintype "passive"))
      (node (ref "R16") (pin "1") (pinfunction "1_1") (pintype "passive"))
    )
    (net (code "23") (name "Net-(D9-C)") (class "Default")
      (node (ref "D9") (pin "1") (pinfunction "C_1") (pintype "passive"))
      (node (ref "R18") (pin "1") (pinfunction "1_1") (pintype "passive"))
    )
    (net (code "24") (name "Net-(D10-C)") (class "Default")
      (node (ref "D10") (pin "1") (pinfunction "C_1") (pintype "passive"))
      (node (ref "R19") (pin "2") (pinfunction "2_2") (pintype "passive"))
    )
    (net (code "25") (name "Net-(D11-C)") (class "Default")
      (node (ref "D11") (pin "1") (pinfunction "C_1") (pintype "passive"))
      (node (ref "R20") (pin "2") (pinfunction "2_2") (pintype "passive"))
    )
    (net (code "26") (name "Net-(D12-C)") (class "Default")
      (node (ref "D12") (pin "1") (pinfunction "C_1") (pintype "passive"))
      (node (ref "R28") (pin "1") (pinfunction "1_1") (pintype "passive"))
    )
    (net (code "27") (name "Net-(D13-A)") (class "Default")
      (node (ref "D13") (pin "1") (pinfunction "A_1") (pintype "passive"))
      (node (ref "Q9") (pin "1") (pinfunction "G_1") (pintype "passive"))
      (node (ref "R22") (pin "2") (pinfunction "2_2") (pintype "passive"))
      (node (ref "R25") (pin "1") (pinfunction "1_1") (pintype "passive"))
    )
    (net (code "28") (name "Net-(D14-C)") (class "Default")
      (node (ref "D14") (pin "1") (pinfunction "C_1") (pintype "passive"))
      (node (ref "R29") (pin "2") (pinfunction "2_2") (pintype "passive"))
    )
    (net (code "29") (name "Net-(D15-A)") (class "Default")
      (node (ref "D15") (pin "1") (pinfunction "A_1") (pintype "passive"))
      (node (ref "Q10") (pin "1") (pinfunction "G_1") (pintype "passive"))
      (node (ref "R26") (pin "2") (pinfunction "2_2") (pintype "passive"))
      (node (ref "R30") (pin "1") (pinfunction "1_1") (pintype "passive"))
    )
    (net (code "30") (name "Net-(D16-A)") (class "Default")
      (node (ref "D16") (pin "1") (pinfunction "A_1") (pintype "passive"))
      (node (ref "Q12") (pin "1") (pinfunction "G_1") (pintype "passive"))
      (node (ref "R33") (pin "2") (pinfunction "2_2") (pintype "passive"))
      (node (ref "R34") (pin "1") (pinfunction "1_1") (pintype "passive"))
    )
    (net (code "31") (name "Net-(D17-C)") (class "Default")
      (node (ref "D17") (pin "1") (pinfunction "C_1") (pintype "passive"))
      (node (ref "R35") (pin "1") (pinfunction "1_1") (pintype "passive"))
    )
    (net (code "32") (name "Net-(D18-C)") (class "Default")
      (node (ref "D18") (pin "1") (pinfunction "C_1") (pintype "passive"))
      (node (ref "R36") (pin "1") (pinfunction "1_1") (pintype "passive"))
    )
    (net (code "33") (name "Net-(Q1-D)") (class "Default")
      (node (ref "Q1") (pin "3") (pinfunction "D_3") (pintype "passive"))
      (node (ref "R5") (pin "1") (pinfunction "1_1") (pintype "passive"))
    )
    (net (code "34") (name "Net-(Q1-G)") (class "Default")
      (node (ref "Q1") (pin "1") (pinfunction "G_1") (pintype "passive"))
      (node (ref "R2") (pin "1") (pinfunction "1_1") (pintype "passive"))
      (node (ref "R4") (pin "2") (pinfunction "2_2") (pintype "passive"))
    )
    (net (code "35") (name "Net-(Q3-D)") (class "Default")
      (node (ref "Q3") (pin "3") (pinfunction "D_3") (pintype "passive"))
      (node (ref "R9") (pin "1") (pinfunction "1_1") (pintype "passive"))
    )
    (net (code "36") (name "Net-(Q3-G)") (class "Default")
      (node (ref "Q3") (pin "1") (pinfunction "G_1") (pintype "passive"))
      (node (ref "R10") (pin "2") (pinfunction "2_2") (pintype "passive"))
      (node (ref "R7") (pin "1") (pinfunction "1_1") (pintype "passive"))
    )
    (net (code "37") (name "Net-(Q4-D)") (class "Default")
      (node (ref "Q4") (pin "3") (pinfunction "D_3") (pintype "passive"))
      (node (ref "R15") (pin "1") (pinfunction "1_1") (pintype "passive"))
    )
    (net (code "38") (name "Net-(Q4-G)") (class "Default")
      (node (ref "Q4") (pin "1") (pinfunction "G_1") (pintype "passive"))
      (node (ref "R12") (pin "1") (pinfunction "1_1") (pintype "passive"))
      (node (ref "R14") (pin "2") (pinfunction "2_2") (pintype "passive"))
    )
    (net (code "39") (name "Net-(Q7-D)") (class "Default")
      (node (ref "Q7") (pin "3") (pinfunction "D_3") (pintype "passive"))
      (node (ref "R22") (pin "1") (pinfunction "1_1") (pintype "passive"))
    )
    (net (code "40") (name "Net-(Q7-G)") (class "Default")
      (node (ref "Q7") (pin "1") (pinfunction "G_1") (pintype "passive"))
      (node (ref "R21") (pin "1") (pinfunction "1_1") (pintype "passive"))
      (node (ref "R23") (pin "2") (pinfunction "2_2") (pintype "passive"))
    )
    (net (code "41") (name "Net-(Q8-D)") (class "Default")
      (node (ref "Q8") (pin "3") (pinfunction "D_3") (pintype "passive"))
      (node (ref "R26") (pin "1") (pinfunction "1_1") (pintype "passive"))
    )
    (net (code "42") (name "Net-(Q8-G)") (class "Default")
      (node (ref "Q8") (pin "1") (pinfunction "G_1") (pintype "passive"))
      (node (ref "R24") (pin "1") (pinfunction "1_1") (pintype "passive"))
      (node (ref "R27") (pin "2") (pinfunction "2_2") (pintype "passive"))
    )
    (net (code "43") (name "Net-(Q11-D)") (class "Default")
      (node (ref "Q11") (pin "3") (pinfunction "D_3") (pintype "passive"))
      (node (ref "R33") (pin "1") (pinfunction "1_1") (pintype "passive"))
    )
    (net (code "44") (name "Net-(Q11-G)") (class "Default")
      (node (ref "Q11") (pin "1") (pinfunction "G_1") (pintype "passive"))
      (node (ref "R31") (pin "1") (pinfunction "1_1") (pintype "passive"))
      (node (ref "R32") (pin "2") (pinfunction "2_2") (pintype "passive"))
    )
    (net (code "45") (name "unconnected-(D4-NC-Pad2)") (class "Default")
      (node (ref "D4") (pin "2") (pinfunction "NC_2") (pintype "passive+no_connect"))
    )
    (net (code "46") (name "unconnected-(D6-NC-Pad2)") (class "Default")
      (node (ref "D6") (pin "2") (pinfunction "NC_2") (pintype "passive+no_connect"))
    )
    (net (code "47") (name "unconnected-(D8-NC-Pad2)") (class "Default")
      (node (ref "D8") (pin "2") (pinfunction "NC_2") (pintype "passive+no_connect"))
    )
    (net (code "48") (name "unconnected-(D13-NC-Pad2)") (class "Default")
      (node (ref "D13") (pin "2") (pinfunction "NC_2") (pintype "passive+no_connect"))
    )
    (net (code "49") (name "unconnected-(D15-NC-Pad2)") (class "Default")
      (node (ref "D15") (pin "2") (pinfunction "NC_2") (pintype "passive+no_connect"))
    )
    (net (code "50") (name "unconnected-(D16-NC-Pad2)") (class "Default")
      (node (ref "D16") (pin "2") (pinfunction "NC_2") (pintype "passive+no_connect"))
    )
    (net (code "51") (name "unconnected-(J7-MNT_1-Pad8)") (class "Default")
      (node (ref "J7") (pin "8") (pinfunction "MNT_1_8") (pintype "passive"))
    )
    (net (code "52") (name "unconnected-(J7-MNT_2-Pad9)") (class "Default")
      (node (ref "J7") (pin "9") (pinfunction "MNT_2_9") (pintype "passive"))
    )
  )
)
